# pro_mini_v0_4.net
KiCad netlist of a schematic drawn in EAGLE
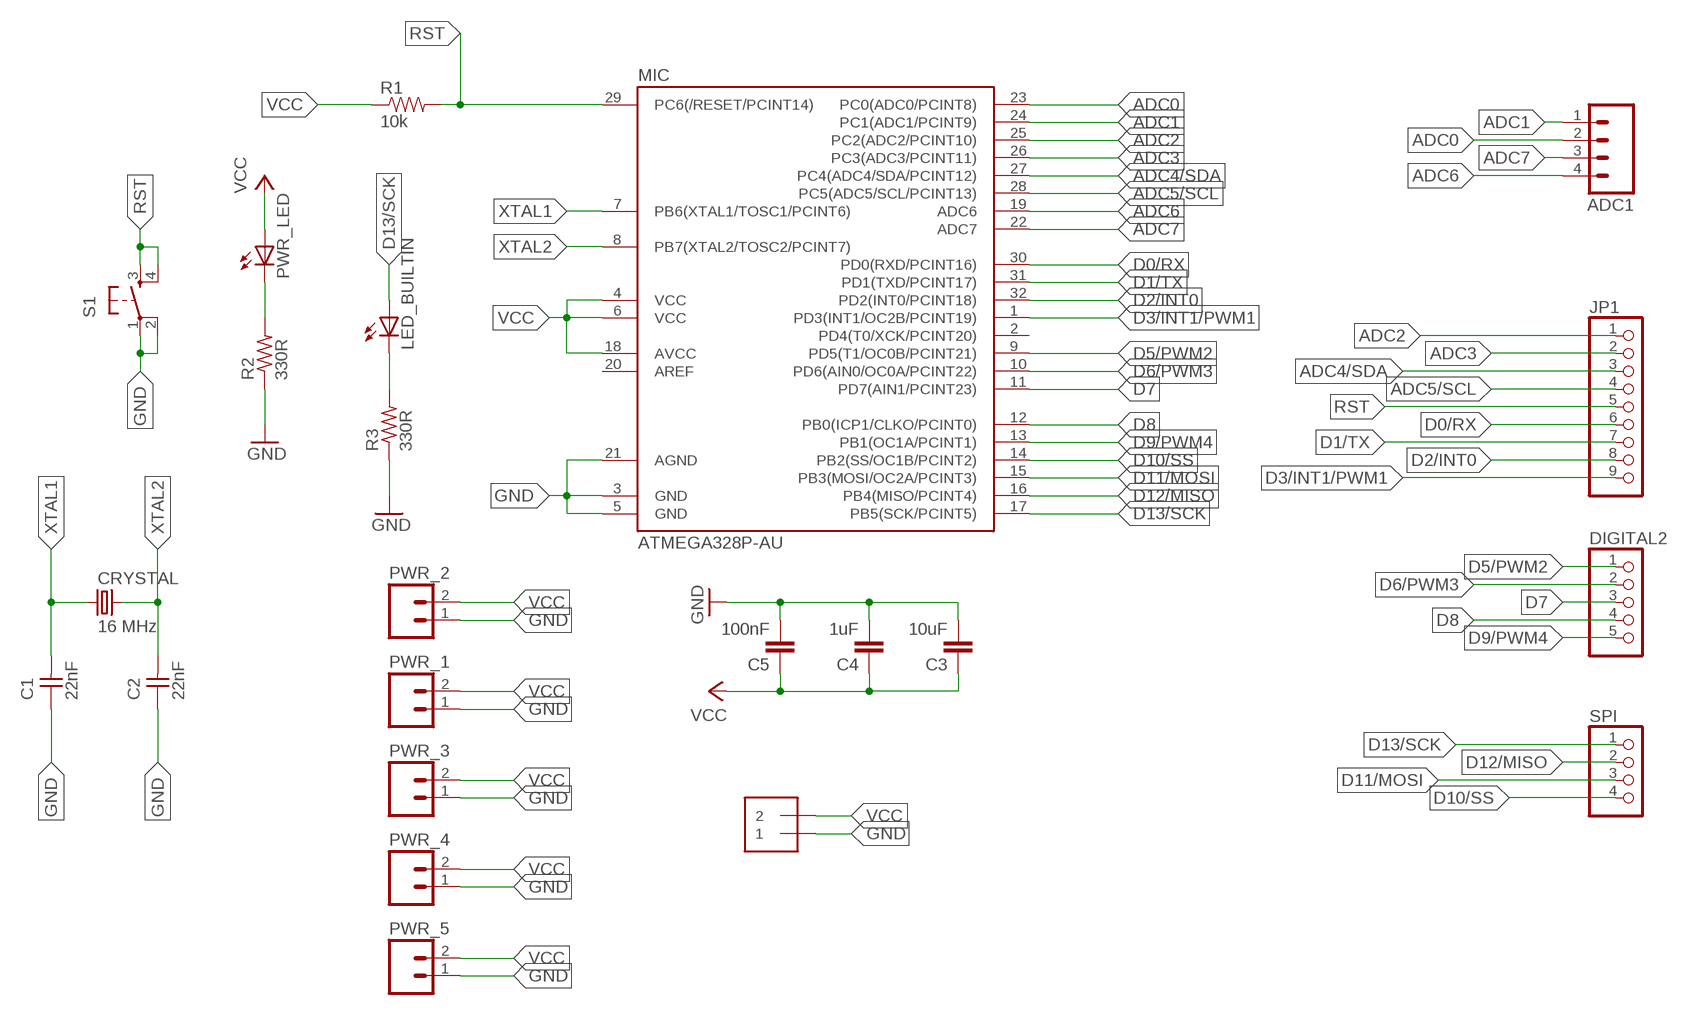
[diagram p0: schematic, sheet 1]

(export (version "E")
  (design (tool "Eeschema 10.0.6"))
  (components
    (comp (ref "ADC1")
      (value "M04LONGPADS")
      (footprint "eagle-import:1X04_LONGPADS")
      (libsource (lib "eagle-import") (part "M04LONGPADS"))
    )
    (comp (ref "C1")
      (value "22nF")
      (footprint "eagle-import:C1206FAB")
      (libsource (lib "eagle-import") (part "CAP-UNPOLARIZEDFAB"))
    )
    (comp (ref "C2")
      (value "22nF")
      (footprint "eagle-import:C1206FAB")
      (libsource (lib "eagle-import") (part "CAP-UNPOLARIZEDFAB"))
    )
    (comp (ref "C3")
      (value "10uF")
      (footprint "eagle-import:1206")
      (libsource (lib "eagle-import") (part "CAP1206"))
    )
    (comp (ref "C4")
      (value "1uF")
      (footprint "eagle-import:1206")
      (libsource (lib "eagle-import") (part "CAP1206"))
    )
    (comp (ref "C5")
      (value "100nF")
      (footprint "eagle-import:1206")
      (libsource (lib "eagle-import") (part "CAP1206"))
    )
    (comp (ref "CRYSTAL")
      (value "16 MHz")
      (footprint "eagle-import:2-SMD-5X3MM")
      (libsource (lib "eagle-import") (part "CRYSTAL"))
    )
    (comp (ref "DIGITAL2")
      (value "PINHD-1X5")
      (footprint "eagle-import:1X05")
      (libsource (lib "eagle-import") (part "PINHD-1X5"))
    )
    (comp (ref "JP1")
      (value "PINHD-1X9")
      (footprint "eagle-import:1X09")
      (libsource (lib "eagle-import") (part "PINHD-1X9"))
    )
    (comp (ref "LED_BUILTIN")
      (value "LED1206")
      (footprint "eagle-import:1206")
      (libsource (lib "eagle-import") (part "LED1206"))
    )
    (comp (ref "MIC")
      (value "ATMEGA328P-AU")
      (footprint "eagle-import:TQFP32-08")
      (libsource (lib "eagle-import") (part "ATMEGA48/88/168-AU"))
    )
    (comp (ref "PWR_1")
      (value "M02LOCK_LONGPADS")
      (footprint "eagle-import:1X02_LOCK_LONGPADS")
      (libsource (lib "eagle-import") (part "M02LOCK_LONGPADS"))
    )
    (comp (ref "PWR_2")
      (value "M02LOCK_LONGPADS")
      (footprint "eagle-import:1X02_LOCK_LONGPADS")
      (libsource (lib "eagle-import") (part "M02LOCK_LONGPADS"))
    )
    (comp (ref "PWR_3")
      (value "M02LOCK_LONGPADS")
      (footprint "eagle-import:1X02_LOCK_LONGPADS")
      (libsource (lib "eagle-import") (part "M02LOCK_LONGPADS"))
    )
    (comp (ref "PWR_4")
      (value "M02LOCK_LONGPADS")
      (footprint "eagle-import:1X02_LOCK_LONGPADS")
      (libsource (lib "eagle-import") (part "M02LOCK_LONGPADS"))
    )
    (comp (ref "PWR_5")
      (value "M02LOCK_LONGPADS")
      (footprint "eagle-import:1X02_LOCK_LONGPADS")
      (libsource (lib "eagle-import") (part "M02LOCK_LONGPADS"))
    )
    (comp (ref "PWR_LED")
      (value "LED1206")
      (footprint "eagle-import:1206")
      (libsource (lib "eagle-import") (part "LED1206"))
    )
    (comp (ref "R1")
      (value "10k")
      (footprint "eagle-import:1206")
      (libsource (lib "eagle-import") (part "RESISTOR1206"))
    )
    (comp (ref "R2")
      (value "330R")
      (footprint "eagle-import:1206")
      (libsource (lib "eagle-import") (part "FAB_Hello_RESISTOR1206"))
    )
    (comp (ref "R3")
      (value "330R")
      (footprint "eagle-import:1206")
      (libsource (lib "eagle-import") (part "FAB_Hello_RESISTOR1206"))
    )
    (comp (ref "S1")
      (value "6MM_SWITCH6MM_SWITCH")
      (footprint "eagle-import:6MM_SWITCH")
      (libsource (lib "eagle-import") (part "6MM_SWITCH6MM_SWITCH"))
    )
    (comp (ref "SPI")
      (value "PINHD-1X4")
      (footprint "eagle-import:1X04")
      (libsource (lib "eagle-import") (part "PINHD-1X4"))
    )
    (comp (ref "VIN")
      (value "1X2-3.5MM")
      (footprint "eagle-import:1X2-3.5MM")
      (libsource (lib "eagle-import") (part "1X2-3.5MM"))
    )
  )
  (nets
    (net (code "1") (name "ADC0") (class "Default")
      (node (ref "ADC1") (pin "2") (pinfunction "2_2") (pintype "passive"))
      (node (ref "MIC") (pin "23") (pinfunction "PC0(ADC0/PCINT8)_23") (pintype "bidirectional"))
    )
    (net (code "2") (name "ADC1") (class "Default")
      (node (ref "ADC1") (pin "1") (pinfunction "1_1") (pintype "passive"))
      (node (ref "MIC") (pin "24") (pinfunction "PC1(ADC1/PCINT9)_24") (pintype "bidirectional"))
    )
    (net (code "3") (name "ADC2") (class "Default")
      (node (ref "JP1") (pin "1") (pinfunction "1_1") (pintype "passive"))
      (node (ref "MIC") (pin "25") (pinfunction "PC2(ADC2/PCINT10)_25") (pintype "bidirectional"))
    )
    (net (code "4") (name "ADC3") (class "Default")
      (node (ref "JP1") (pin "2") (pinfunction "2_2") (pintype "passive"))
      (node (ref "MIC") (pin "26") (pinfunction "PC3(ADC3/PCINT11)_26") (pintype "bidirectional"))
    )
    (net (code "5") (name "ADC4{slash}SDA") (class "Default")
      (node (ref "JP1") (pin "3") (pinfunction "3_3") (pintype "passive"))
      (node (ref "MIC") (pin "27") (pinfunction "PC4(ADC4/SDA/PCINT12)_27") (pintype "bidirectional"))
    )
    (net (code "6") (name "ADC5{slash}SCL") (class "Default")
      (node (ref "JP1") (pin "4") (pinfunction "4_4") (pintype "passive"))
      (node (ref "MIC") (pin "28") (pinfunction "PC5(ADC5/SCL/PCINT13)_28") (pintype "bidirectional"))
    )
    (net (code "7") (name "ADC6") (class "Default")
      (node (ref "ADC1") (pin "4") (pinfunction "4_4") (pintype "passive"))
      (node (ref "MIC") (pin "19") (pinfunction "ADC6_19") (pintype "passive"))
    )
    (net (code "8") (name "ADC7") (class "Default")
      (node (ref "ADC1") (pin "3") (pinfunction "3_3") (pintype "passive"))
      (node (ref "MIC") (pin "22") (pinfunction "ADC7_22") (pintype "passive"))
    )
    (net (code "9") (name "D0{slash}RX") (class "Default")
      (node (ref "JP1") (pin "6") (pinfunction "6_6") (pintype "passive"))
      (node (ref "MIC") (pin "30") (pinfunction "PD0(RXD/PCINT16)_30") (pintype "bidirectional"))
    )
    (net (code "10") (name "D1{slash}TX") (class "Default")
      (node (ref "JP1") (pin "7") (pinfunction "7_7") (pintype "passive"))
      (node (ref "MIC") (pin "31") (pinfunction "PD1(TXD/PCINT17)_31") (pintype "bidirectional"))
    )
    (net (code "11") (name "D2{slash}INT0") (class "Default")
      (node (ref "JP1") (pin "8") (pinfunction "8_8") (pintype "passive"))
      (node (ref "MIC") (pin "32") (pinfunction "PD2(INT0/PCINT18)_32") (pintype "bidirectional"))
    )
    (net (code "12") (name "D3{slash}INT1{slash}PWM1") (class "Default")
      (node (ref "JP1") (pin "9") (pinfunction "9_9") (pintype "passive"))
      (node (ref "MIC") (pin "1") (pinfunction "PD3(INT1/OC2B/PCINT19)_1") (pintype "bidirectional"))
    )
    (net (code "13") (name "D5{slash}PWM2") (class "Default")
      (node (ref "DIGITAL2") (pin "1") (pinfunction "1_1") (pintype "passive"))
      (node (ref "MIC") (pin "9") (pinfunction "PD5(T1/OC0B/PCINT21)_9") (pintype "bidirectional"))
    )
    (net (code "14") (name "D6{slash}PWM3") (class "Default")
      (node (ref "DIGITAL2") (pin "2") (pinfunction "2_2") (pintype "passive"))
      (node (ref "MIC") (pin "10") (pinfunction "PD6(AIN0/OC0A/PCINT22)_10") (pintype "bidirectional"))
    )
    (net (code "15") (name "D7") (class "Default")
      (node (ref "DIGITAL2") (pin "3") (pinfunction "3_3") (pintype "passive"))
      (node (ref "MIC") (pin "11") (pinfunction "PD7(AIN1/PCINT23)_11") (pintype "bidirectional"))
    )
    (net (code "16") (name "D8") (class "Default")
      (node (ref "DIGITAL2") (pin "4") (pinfunction "4_4") (pintype "passive"))
      (node (ref "MIC") (pin "12") (pinfunction "PB0(ICP1/CLKO/PCINT0)_12") (pintype "bidirectional"))
    )
    (net (code "17") (name "D9{slash}PWM4") (class "Default")
      (node (ref "DIGITAL2") (pin "5") (pinfunction "5_5") (pintype "passive"))
      (node (ref "MIC") (pin "13") (pinfunction "PB1(OC1A/PCINT1)_13") (pintype "bidirectional"))
    )
    (net (code "18") (name "D10{slash}SS") (class "Default")
      (node (ref "MIC") (pin "14") (pinfunction "PB2(SS/OC1B/PCINT2)_14") (pintype "bidirectional"))
      (node (ref "SPI") (pin "4") (pinfunction "4_4") (pintype "passive"))
    )
    (net (code "19") (name "D11{slash}MOSI") (class "Default")
      (node (ref "MIC") (pin "15") (pinfunction "PB3(MOSI/OC2A/PCINT3)_15") (pintype "bidirectional"))
      (node (ref "SPI") (pin "3") (pinfunction "3_3") (pintype "passive"))
    )
    (net (code "20") (name "D12{slash}MISO") (class "Default")
      (node (ref "MIC") (pin "16") (pinfunction "PB4(MISO/PCINT4)_16") (pintype "bidirectional"))
      (node (ref "SPI") (pin "2") (pinfunction "2_2") (pintype "passive"))
    )
    (net (code "21") (name "D13{slash}SCK") (class "Default")
      (node (ref "LED_BUILTIN") (pin "1") (pinfunction "A_1") (pintype "passive"))
      (node (ref "MIC") (pin "17") (pinfunction "PB5(SCK/PCINT5)_17") (pintype "bidirectional"))
      (node (ref "SPI") (pin "1") (pinfunction "1_1") (pintype "passive"))
    )
    (net (code "22") (name "GND") (class "Default")
      (node (ref "C1") (pin "1") (pinfunction "1_1") (pintype "passive"))
      (node (ref "C2") (pin "1") (pinfunction "1_1") (pintype "passive"))
      (node (ref "C3") (pin "2") (pinfunction "2_2") (pintype "passive"))
      (node (ref "C4") (pin "2") (pinfunction "2_2") (pintype "passive"))
      (node (ref "C5") (pin "2") (pinfunction "2_2") (pintype "passive"))
      (node (ref "MIC") (pin "21") (pinfunction "AGND_21") (pintype "power_in"))
      (node (ref "MIC") (pin "3") (pinfunction "GND_3") (pintype "power_in"))
      (node (ref "MIC") (pin "5") (pinfunction "GND_5") (pintype "power_in"))
      (node (ref "PWR_1") (pin "1") (pinfunction "1_1") (pintype "passive"))
      (node (ref "PWR_2") (pin "1") (pinfunction "1_1") (pintype "passive"))
      (node (ref "PWR_3") (pin "1") (pinfunction "1_1") (pintype "passive"))
      (node (ref "PWR_4") (pin "1") (pinfunction "1_1") (pintype "passive"))
      (node (ref "PWR_5") (pin "1") (pinfunction "1_1") (pintype "passive"))
      (node (ref "R2") (pin "1") (pinfunction "1_1") (pintype "passive"))
      (node (ref "R3") (pin "1") (pinfunction "1_1") (pintype "passive"))
      (node (ref "S1") (pin "1") (pinfunction "P_1") (pintype "passive"))
      (node (ref "S1") (pin "2") (pinfunction "P1_2") (pintype "passive"))
      (node (ref "VIN") (pin "1") (pinfunction "1_1") (pintype "passive"))
    )
    (net (code "23") (name "Net-(LED_BUILTIN-C)") (class "Default")
      (node (ref "LED_BUILTIN") (pin "2") (pinfunction "C_2") (pintype "passive"))
      (node (ref "R3") (pin "2") (pinfunction "2_2") (pintype "passive"))
    )
    (net (code "24") (name "Net-(PWR_LED-C)") (class "Default")
      (node (ref "PWR_LED") (pin "2") (pinfunction "C_2") (pintype "passive"))
      (node (ref "R2") (pin "2") (pinfunction "2_2") (pintype "passive"))
    )
    (net (code "25") (name "RST") (class "Default")
      (node (ref "JP1") (pin "5") (pinfunction "5_5") (pintype "passive"))
      (node (ref "MIC") (pin "29") (pinfunction "PC6(/RESET/PCINT14)_29") (pintype "bidirectional"))
      (node (ref "R1") (pin "2") (pinfunction "2_2") (pintype "passive"))
      (node (ref "S1") (pin "3") (pinfunction "S_3") (pintype "passive"))
      (node (ref "S1") (pin "4") (pinfunction "S1_4") (pintype "passive"))
    )
    (net (code "26") (name "VCC") (class "Default")
      (node (ref "C3") (pin "1") (pinfunction "1_1") (pintype "passive"))
      (node (ref "C4") (pin "1") (pinfunction "1_1") (pintype "passive"))
      (node (ref "C5") (pin "1") (pinfunction "1_1") (pintype "passive"))
      (node (ref "MIC") (pin "18") (pinfunction "AVCC_18") (pintype "passive"))
      (node (ref "MIC") (pin "4") (pinfunction "VCC_4") (pintype "power_in"))
      (node (ref "MIC") (pin "6") (pinfunction "VCC_6") (pintype "power_in"))
      (node (ref "PWR_1") (pin "2") (pinfunction "2_2") (pintype "passive"))
      (node (ref "PWR_2") (pin "2") (pinfunction "2_2") (pintype "passive"))
      (node (ref "PWR_3") (pin "2") (pinfunction "2_2") (pintype "passive"))
      (node (ref "PWR_4") (pin "2") (pinfunction "2_2") (pintype "passive"))
      (node (ref "PWR_5") (pin "2") (pinfunction "2_2") (pintype "passive"))
      (node (ref "PWR_LED") (pin "1") (pinfunction "A_1") (pintype "passive"))
      (node (ref "R1") (pin "1") (pinfunction "1_1") (pintype "passive"))
      (node (ref "VIN") (pin "2") (pinfunction "2_2") (pintype "passive"))
    )
    (net (code "27") (name "XTAL1") (class "Default")
      (node (ref "C1") (pin "2") (pinfunction "2_2") (pintype "passive"))
      (node (ref "CRYSTAL") (pin "P$1") (pinfunction "1_P$1") (pintype "passive"))
      (node (ref "MIC") (pin "7") (pinfunction "PB6(XTAL1/TOSC1/PCINT6)_7") (pintype "bidirectional"))
    )
    (net (code "28") (name "XTAL2") (class "Default")
      (node (ref "C2") (pin "2") (pinfunction "2_2") (pintype "passive"))
      (node (ref "CRYSTAL") (pin "P$2") (pinfunction "2_P$2") (pintype "passive"))
      (node (ref "MIC") (pin "8") (pinfunction "PB7(XTAL2/TOSC2/PCINT7)_8") (pintype "bidirectional"))
    )
    (net (code "29") (name "unconnected-(MIC-AREF-Pad20)") (class "Default")
      (node (ref "MIC") (pin "20") (pinfunction "AREF_20") (pintype "passive"))
    )
    (net (code "30") (name "unconnected-(MIC-PD4(T0{slash}XCK{slash}PCINT20)-Pad2)") (class "Default")
      (node (ref "MIC") (pin "2") (pinfunction "PD4(T0/XCK/PCINT20)_2") (pintype "bidirectional"))
    )
  )
)
